# User_Interface_5.net
KiCad netlist of a schematic drawn in EAGLE
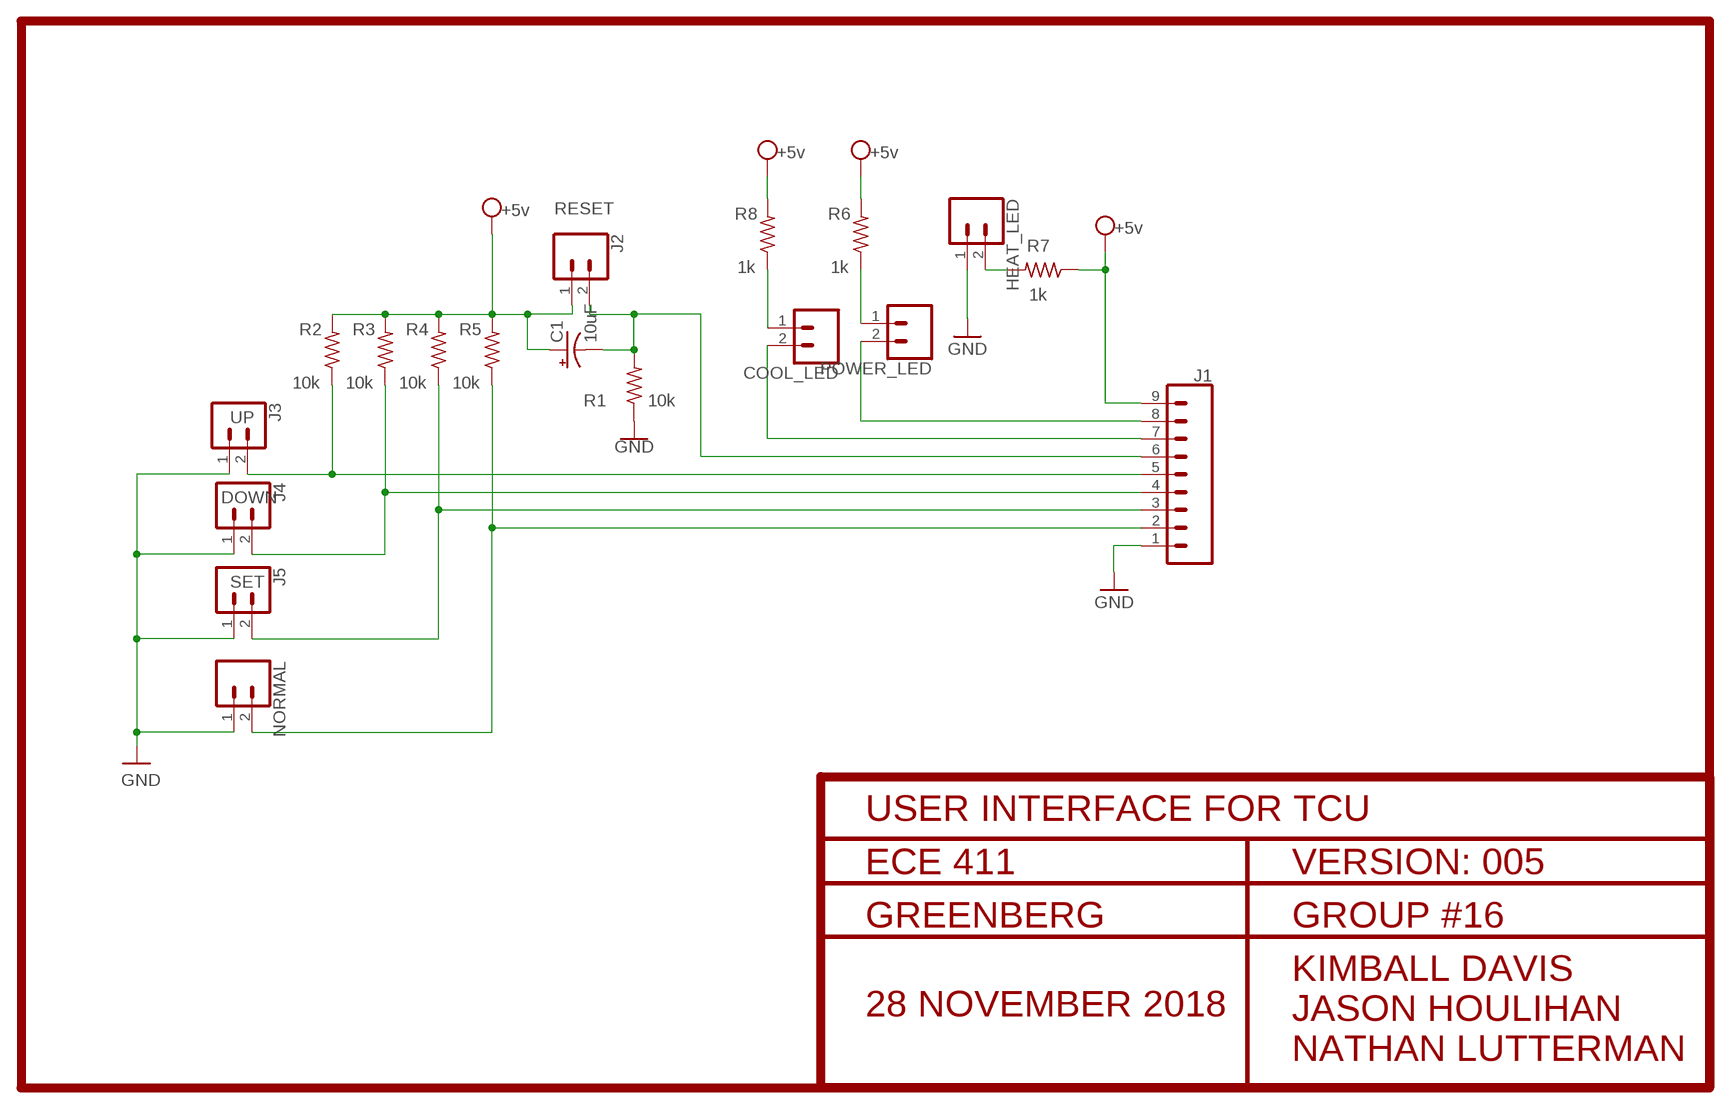
[diagram p0: schematic, sheet 1]

(export (version "E")
  (design (tool "Eeschema 10.0.6"))
  (components
    (comp (ref "C1")
      (value "10uF")
      (footprint "eagle-import:CPOL-RADIAL-2.5MM-5MM")
      (libsource (lib "eagle-import") (part "10UF-POLAR-RADIAL-2.5MM-25V-20%"))
    )
    (comp (ref "COOL_LED")
      (value "CONN_02")
      (footprint "eagle-import:1X02")
      (libsource (lib "eagle-import") (part "CONN_02"))
    )
    (comp (ref "HEAT_LED")
      (value "CONN_02")
      (footprint "eagle-import:1X02")
      (libsource (lib "eagle-import") (part "CONN_02"))
    )
    (comp (ref "J1")
      (value "CONN_09")
      (footprint "eagle-import:1X09")
      (libsource (lib "eagle-import") (part "CONN_09"))
    )
    (comp (ref "J2")
      (value "RESET")
      (footprint "eagle-import:1X02")
      (libsource (lib "eagle-import") (part "CONN_02"))
    )
    (comp (ref "J3")
      (value "UP")
      (footprint "eagle-import:1X02")
      (libsource (lib "eagle-import") (part "CONN_02"))
    )
    (comp (ref "J4")
      (value "DOWN")
      (footprint "eagle-import:1X02")
      (libsource (lib "eagle-import") (part "CONN_02"))
    )
    (comp (ref "J5")
      (value "SET")
      (footprint "eagle-import:1X02")
      (libsource (lib "eagle-import") (part "CONN_02"))
    )
    (comp (ref "NORMAL")
      (value "CONN_02")
      (footprint "eagle-import:1X02")
      (libsource (lib "eagle-import") (part "CONN_02"))
    )
    (comp (ref "POWER_LED")
      (value "CONN_02")
      (footprint "eagle-import:1X02")
      (libsource (lib "eagle-import") (part "CONN_02"))
    )
    (comp (ref "R1")
      (value "10k")
      (footprint "eagle-import:R0603")
      (libsource (lib "eagle-import") (part "R-US_R0603"))
    )
    (comp (ref "R2")
      (value "10k")
      (footprint "eagle-import:R0603")
      (libsource (lib "eagle-import") (part "R-US_R0603"))
    )
    (comp (ref "R3")
      (value "10k")
      (footprint "eagle-import:R0603")
      (libsource (lib "eagle-import") (part "R-US_R0603"))
    )
    (comp (ref "R4")
      (value "10k")
      (footprint "eagle-import:R0603")
      (libsource (lib "eagle-import") (part "R-US_R0603"))
    )
    (comp (ref "R5")
      (value "10k")
      (footprint "eagle-import:R0603")
      (libsource (lib "eagle-import") (part "R-US_R0603"))
    )
    (comp (ref "R6")
      (value "1k")
      (footprint "eagle-import:R0603")
      (libsource (lib "eagle-import") (part "R-US_R0603"))
    )
    (comp (ref "R7")
      (value "1k")
      (footprint "eagle-import:R0603")
      (libsource (lib "eagle-import") (part "R-US_R0603"))
    )
    (comp (ref "R8")
      (value "1k")
      (footprint "eagle-import:R0603")
      (libsource (lib "eagle-import") (part "R-US_R0603"))
    )
  )
  (nets
    (net (code "1") (name "+5v") (class "Default")
      (node (ref "C1") (pin "1") (pinfunction "+_1") (pintype "passive"))
      (node (ref "J1") (pin "9") (pinfunction "9_9") (pintype "passive"))
      (node (ref "J2") (pin "1") (pinfunction "1_1") (pintype "passive"))
      (node (ref "R2") (pin "2") (pinfunction "2_2") (pintype "passive"))
      (node (ref "R3") (pin "2") (pinfunction "2_2") (pintype "passive"))
      (node (ref "R4") (pin "2") (pinfunction "2_2") (pintype "passive"))
      (node (ref "R5") (pin "2") (pinfunction "2_2") (pintype "passive"))
      (node (ref "R6") (pin "2") (pinfunction "2_2") (pintype "passive"))
      (node (ref "R7") (pin "1") (pinfunction "1_1") (pintype "passive"))
      (node (ref "R8") (pin "2") (pinfunction "2_2") (pintype "passive"))
    )
    (net (code "2") (name "GND") (class "Default")
      (node (ref "HEAT_LED") (pin "1") (pinfunction "1_1") (pintype "passive"))
      (node (ref "J1") (pin "1") (pinfunction "1_1") (pintype "passive"))
      (node (ref "J3") (pin "1") (pinfunction "1_1") (pintype "passive"))
      (node (ref "J4") (pin "1") (pinfunction "1_1") (pintype "passive"))
      (node (ref "J5") (pin "1") (pinfunction "1_1") (pintype "passive"))
      (node (ref "NORMAL") (pin "1") (pinfunction "1_1") (pintype "passive"))
      (node (ref "R1") (pin "1") (pinfunction "1_1") (pintype "passive"))
    )
    (net (code "3") (name "Net-(C1--)") (class "Default")
      (node (ref "C1") (pin "2") (pinfunction "-_2") (pintype "passive"))
      (node (ref "J1") (pin "6") (pinfunction "6_6") (pintype "passive"))
      (node (ref "J2") (pin "2") (pinfunction "2_2") (pintype "passive"))
      (node (ref "R1") (pin "2") (pinfunction "2_2") (pintype "passive"))
    )
    (net (code "4") (name "Net-(COOL_LED-Pad1)") (class "Default")
      (node (ref "COOL_LED") (pin "1") (pinfunction "1_1") (pintype "passive"))
      (node (ref "R8") (pin "1") (pinfunction "1_1") (pintype "passive"))
    )
    (net (code "5") (name "Net-(COOL_LED-Pad2)") (class "Default")
      (node (ref "COOL_LED") (pin "2") (pinfunction "2_2") (pintype "passive"))
      (node (ref "J1") (pin "7") (pinfunction "7_7") (pintype "passive"))
    )
    (net (code "6") (name "Net-(HEAT_LED-Pad2)") (class "Default")
      (node (ref "HEAT_LED") (pin "2") (pinfunction "2_2") (pintype "passive"))
      (node (ref "R7") (pin "2") (pinfunction "2_2") (pintype "passive"))
    )
    (net (code "7") (name "Net-(J1-Pad2)") (class "Default")
      (node (ref "J1") (pin "2") (pinfunction "2_2") (pintype "passive"))
      (node (ref "NORMAL") (pin "2") (pinfunction "2_2") (pintype "passive"))
      (node (ref "R5") (pin "1") (pinfunction "1_1") (pintype "passive"))
    )
    (net (code "8") (name "Net-(J1-Pad3)") (class "Default")
      (node (ref "J1") (pin "3") (pinfunction "3_3") (pintype "passive"))
      (node (ref "J5") (pin "2") (pinfunction "2_2") (pintype "passive"))
      (node (ref "R4") (pin "1") (pinfunction "1_1") (pintype "passive"))
    )
    (net (code "9") (name "Net-(J1-Pad4)") (class "Default")
      (node (ref "J1") (pin "4") (pinfunction "4_4") (pintype "passive"))
      (node (ref "J4") (pin "2") (pinfunction "2_2") (pintype "passive"))
      (node (ref "R3") (pin "1") (pinfunction "1_1") (pintype "passive"))
    )
    (net (code "10") (name "Net-(J1-Pad5)") (class "Default")
      (node (ref "J1") (pin "5") (pinfunction "5_5") (pintype "passive"))
      (node (ref "J3") (pin "2") (pinfunction "2_2") (pintype "passive"))
      (node (ref "R2") (pin "1") (pinfunction "1_1") (pintype "passive"))
    )
    (net (code "11") (name "Net-(J1-Pad8)") (class "Default")
      (node (ref "J1") (pin "8") (pinfunction "8_8") (pintype "passive"))
      (node (ref "POWER_LED") (pin "2") (pinfunction "2_2") (pintype "passive"))
    )
    (net (code "12") (name "Net-(POWER_LED-Pad1)") (class "Default")
      (node (ref "POWER_LED") (pin "1") (pinfunction "1_1") (pintype "passive"))
      (node (ref "R6") (pin "1") (pinfunction "1_1") (pintype "passive"))
    )
  )
)
